# dc_booster.net
KiCad netlist of a schematic drawn in EAGLE
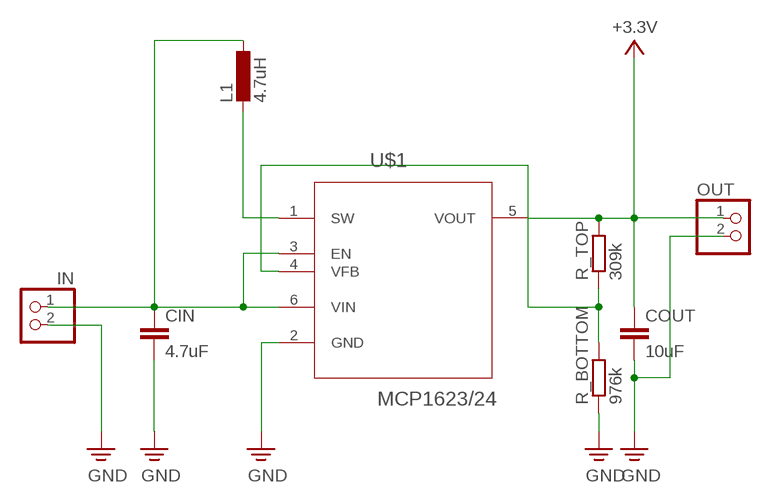
[diagram p0: schematic, sheet 1]

(export (version "E")
  (design (tool "Eeschema 10.0.6"))
  (components
    (comp (ref "CIN")
      (value "4.7uF")
      (footprint "eagle-import:C0805")
      (libsource (lib "eagle-import") (part "C-EUC0805"))
    )
    (comp (ref "COUT")
      (value "10uF")
      (footprint "eagle-import:C0805")
      (libsource (lib "eagle-import") (part "C-EUC0805"))
    )
    (comp (ref "IN")
      (value "PINHD-1X2")
      (footprint "eagle-import:1X02")
      (libsource (lib "eagle-import") (part "PINHD-1X2"))
    )
    (comp (ref "L1")
      (value "4.7uH")
      (footprint "eagle-import:POWER-CHOKE_WE-TPC")
      (libsource (lib "eagle-import") (part "L-EUWE-TPC"))
    )
    (comp (ref "OUT")
      (value "PINHD-1X2")
      (footprint "eagle-import:1X02")
      (libsource (lib "eagle-import") (part "PINHD-1X2"))
    )
    (comp (ref "R_BOTTOM")
      (value "976k")
      (footprint "eagle-import:R0805")
      (libsource (lib "eagle-import") (part "R-EU_R0805"))
    )
    (comp (ref "R_TOP")
      (value "309k")
      (footprint "eagle-import:R0805")
      (libsource (lib "eagle-import") (part "R-EU_R0805"))
    )
    (comp (ref "U$1")
      (value "MCP1623/24")
      (footprint "eagle-import:SOT95P300X120-6N")
      (libsource (lib "eagle-import") (part "MCP1623/24"))
    )
  )
  (nets
    (net (code "1") (name "+3.3V") (class "Default")
      (node (ref "COUT") (pin "1") (pinfunction "1_1") (pintype "passive"))
      (node (ref "OUT") (pin "1") (pinfunction "1_1") (pintype "passive"))
      (node (ref "R_TOP") (pin "2") (pinfunction "2_2") (pintype "passive"))
      (node (ref "U$1") (pin "5") (pinfunction "VOUT_5") (pintype "output"))
    )
    (net (code "2") (name "GND") (class "Default")
      (node (ref "CIN") (pin "2") (pinfunction "2_2") (pintype "passive"))
      (node (ref "COUT") (pin "2") (pinfunction "2_2") (pintype "passive"))
      (node (ref "IN") (pin "2") (pinfunction "2_2") (pintype "passive"))
      (node (ref "OUT") (pin "2") (pinfunction "2_2") (pintype "passive"))
      (node (ref "R_BOTTOM") (pin "1") (pinfunction "1_1") (pintype "passive"))
      (node (ref "U$1") (pin "2") (pinfunction "GND_2") (pintype "passive"))
    )
    (net (code "3") (name "Net-(U$1-EN)") (class "Default")
      (node (ref "CIN") (pin "1") (pinfunction "1_1") (pintype "passive"))
      (node (ref "IN") (pin "1") (pinfunction "1_1") (pintype "passive"))
      (node (ref "L1") (pin "1") (pinfunction "1_1") (pintype "passive"))
      (node (ref "U$1") (pin "3") (pinfunction "EN_3") (pintype "input"))
      (node (ref "U$1") (pin "6") (pinfunction "VIN_6") (pintype "input"))
    )
    (net (code "4") (name "Net-(U$1-SW)") (class "Default")
      (node (ref "L1") (pin "2") (pinfunction "2_2") (pintype "passive"))
      (node (ref "U$1") (pin "1") (pinfunction "SW_1") (pintype "power_in"))
    )
    (net (code "5") (name "Net-(U$1-VFB)") (class "Default")
      (node (ref "R_BOTTOM") (pin "2") (pinfunction "2_2") (pintype "passive"))
      (node (ref "R_TOP") (pin "1") (pinfunction "1_1") (pintype "passive"))
      (node (ref "U$1") (pin "4") (pinfunction "VFB_4") (pintype "input"))
    )
  )
)
